# FMC_AWG_DAC_PSU_LDO.net
KiCad netlist of a schematic drawn in Altium Designer
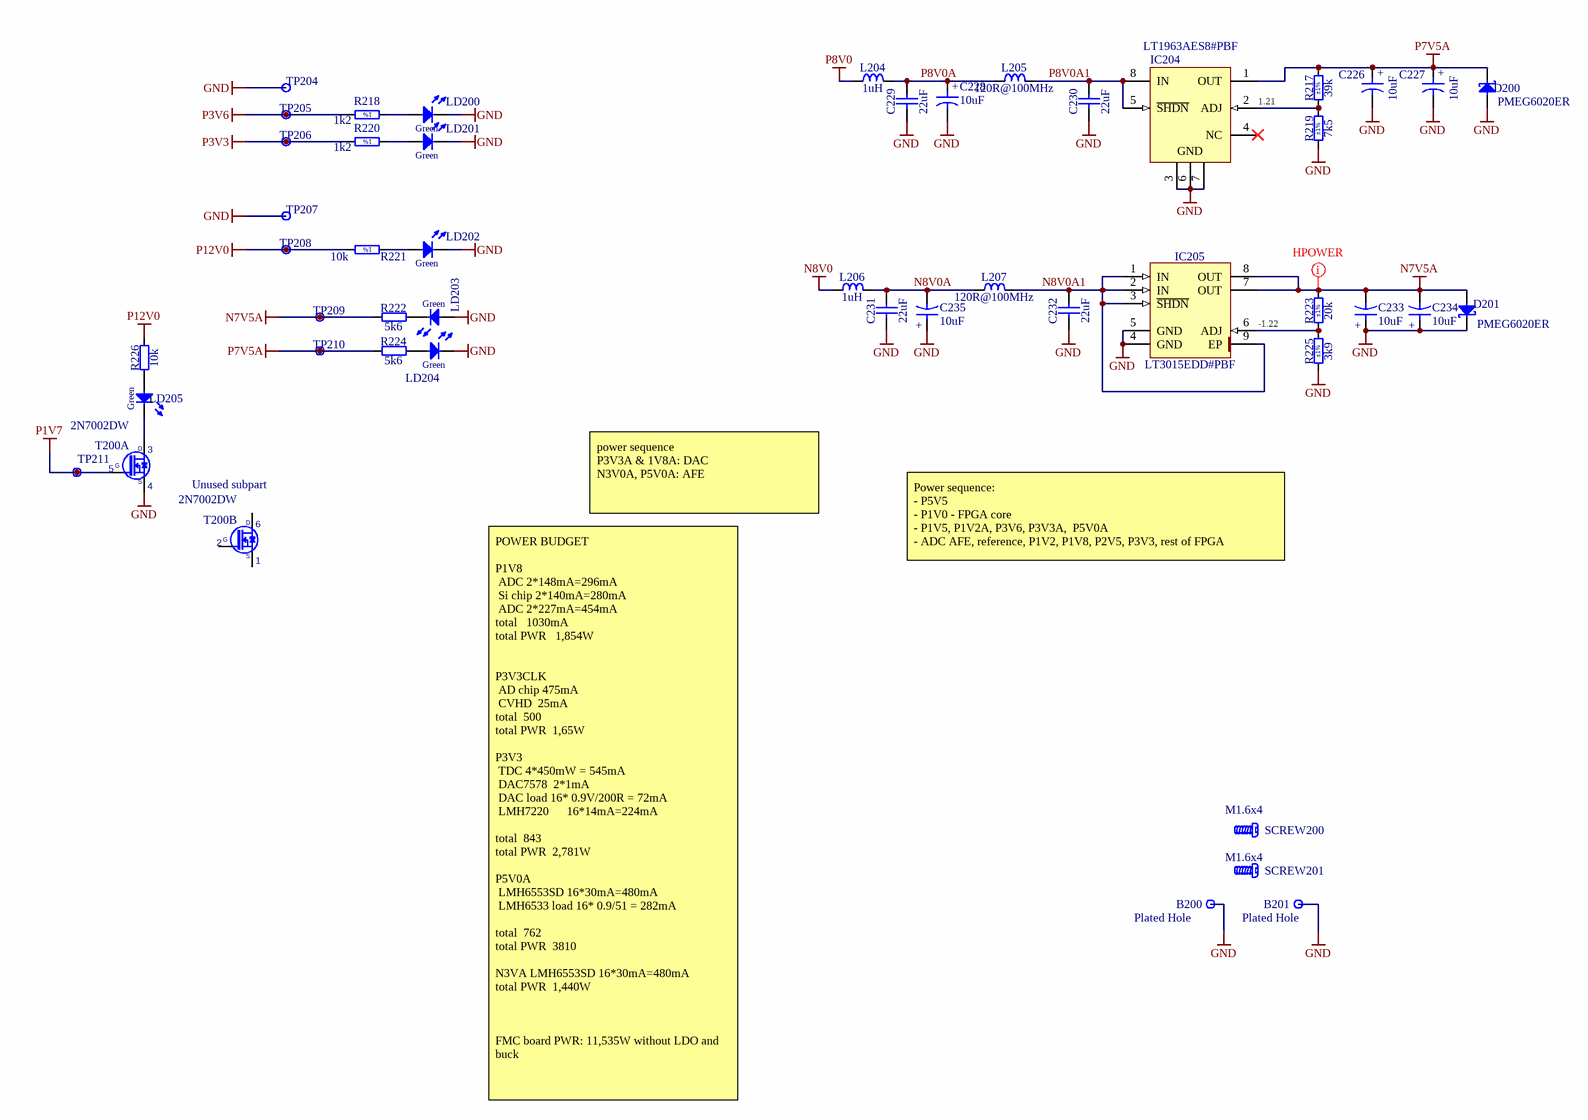
[diagram p0: FMC_AWG_DAC_PSU_LDO.SchDoc]

(export (version "E")
  (design (tool "Eeschema 10.0.6"))
  (components
    (comp (ref "B200")
      (value "Plated Hole")
      (footprint "c300h160")
      (description "Single Terminal Socket")
      (fields (field (name "PART NUMBER") "PLATED_HOLE1.6_PAD3.0") (field (name "AUTHOR") "CERN DEM JMW"))
      (libsource (lib "Eletro-mechanical") (part "Single Terminal Socket"))
    )
    (comp (ref "B201")
      (value "Plated Hole")
      (footprint "c300h160")
      (description "Single Terminal Socket")
      (fields (field (name "PART NUMBER") "PLATED_HOLE1.6_PAD3.0") (field (name "AUTHOR") "CERN DEM JMW"))
      (libsource (lib "Eletro-mechanical") (part "Single Terminal Socket"))
    )
    (comp (ref "C226")
      (value "10uF")
      (footprint "CAPMP3216X180N")
      (description "Polarised capacitor")
      (fields
        (field (name "PART NUMBER") "CTE3216-18_10UF_16V_20%_AVX_TCJ")
        (field (name "VOLTAGE") "16V")
        (field (name "AUTHOR") "CERN DEM JLC")
      )
      (libsource (lib "Capacitors") (part "Capacitor - polarized"))
    )
    (comp (ref "C227")
      (value "10uF")
      (footprint "CAPMP3216X180N")
      (description "Polarised capacitor")
      (fields
        (field (name "PART NUMBER") "CTE3216-18_10UF_16V_20%_AVX_TCJ")
        (field (name "VOLTAGE") "16V")
        (field (name "AUTHOR") "CERN DEM JLC")
      )
      (libsource (lib "Capacitors") (part "Capacitor - polarized"))
    )
    (comp (ref "C228")
      (value "10uF")
      (footprint "CAPMP3216X180N")
      (description "Polarised capacitor")
      (fields
        (field (name "PART NUMBER") "CTE3216-18_10UF_16V_20%_AVX_TCJ")
        (field (name "VOLTAGE") "16V")
        (field (name "AUTHOR") "CERN DEM JLC")
      )
      (libsource (lib "Capacitors") (part "Capacitor - polarized"))
    )
    (comp (ref "C229")
      (value "22uF")
      (footprint "CAPC2012X135N")
      (description "Non-polarised capacitor")
      (fields
        (field (name "PART NUMBER") "CC0805_22UF_16V_10%_X5R")
        (field (name "VOLTAGE") "16V")
        (field (name "AUTHOR") "CERN DEM JLC")
      )
      (libsource (lib "Capacitors") (part "Capacitor - non polarized"))
    )
    (comp (ref "C230")
      (value "22uF")
      (footprint "CAPC2012X135N")
      (description "Non-polarised capacitor")
      (fields
        (field (name "PART NUMBER") "CC0805_22UF_16V_10%_X5R")
        (field (name "VOLTAGE") "16V")
        (field (name "AUTHOR") "CERN DEM JLC")
      )
      (libsource (lib "Capacitors") (part "Capacitor - non polarized"))
    )
    (comp (ref "C231")
      (value "22uF")
      (footprint "CAPC2012X135N")
      (description "Non-polarised capacitor")
      (fields
        (field (name "PART NUMBER") "CC0805_22UF_16V_10%_X5R")
        (field (name "VOLTAGE") "16V")
        (field (name "AUTHOR") "CERN DEM JLC")
      )
      (libsource (lib "Capacitors") (part "Capacitor - non polarized"))
    )
    (comp (ref "C232")
      (value "22uF")
      (footprint "CAPC2012X135N")
      (description "Non-polarised capacitor")
      (fields
        (field (name "PART NUMBER") "CC0805_22UF_16V_10%_X5R")
        (field (name "VOLTAGE") "16V")
        (field (name "AUTHOR") "CERN DEM JLC")
      )
      (libsource (lib "Capacitors") (part "Capacitor - non polarized"))
    )
    (comp (ref "C233")
      (value "10uF")
      (footprint "CAPMP3216X180N")
      (description "Polarised capacitor")
      (fields
        (field (name "PART NUMBER") "CTE3216-18_10UF_16V_20%_AVX_TCJ")
        (field (name "VOLTAGE") "16V")
        (field (name "AUTHOR") "CERN DEM JLC")
      )
      (libsource (lib "Capacitors") (part "Capacitor - polarized"))
    )
    (comp (ref "C234")
      (value "10uF")
      (footprint "CAPMP3216X180N")
      (description "Polarised capacitor")
      (fields
        (field (name "PART NUMBER") "CTE3216-18_10UF_16V_20%_AVX_TCJ")
        (field (name "VOLTAGE") "16V")
        (field (name "AUTHOR") "CERN DEM JLC")
      )
      (libsource (lib "Capacitors") (part "Capacitor - polarized"))
    )
    (comp (ref "C235")
      (value "10uF")
      (footprint "CAPMP3216X180N")
      (description "Polarised capacitor")
      (fields
        (field (name "PART NUMBER") "CTE3216-18_10UF_16V_20%_AVX_TCJ")
        (field (name "VOLTAGE") "16V")
        (field (name "AUTHOR") "CERN DEM JLC")
      )
      (libsource (lib "Capacitors") (part "Capacitor - polarized"))
    )
    (comp (ref "D200")
      (value "PMEG6020ER")
      (footprint "SODFL3517X110N")
      (description "Schottky Diode")
      (fields
        (field (name "VOLTAGE") "60V")
        (field (name "POWER") "2A")
        (field (name "AUTHOR") "CERN DEM JMW")
      )
      (libsource (lib "ICs And Semiconductors") (part "Diode Schottky"))
    )
    (comp (ref "D201")
      (value "PMEG6020ER")
      (footprint "SODFL3517X110N")
      (description "Schottky Diode")
      (fields
        (field (name "VOLTAGE") "60V")
        (field (name "POWER") "2A")
        (field (name "AUTHOR") "CERN DEM JMW")
      )
      (libsource (lib "ICs And Semiconductors") (part "Diode Schottky"))
    )
    (comp (ref "IC204")
      (value "LT1963AES8#PBF")
      (footprint "LT-S8-8_L")
      (fields (field (name "MANUFACTURER") "Linear Technology"))
      (libsource (lib "Altium Content Vault") (part "LT-LT1521_1963A-S8-8_B"))
    )
    (comp (ref "IC205")
      (value "LT3015EDD#PBF")
      (footprint "SON50P300X300X80-9N-R175X248")
      (description "1.5A, Low Noise, Negative Linear Regulator with Precision Current Limit")
      (fields (field (name "MANUFACTURER") "LINEAR TECHNOLOGY") (field (name "AUTHOR") "CERN DEM MR"))
      (libsource (lib "ICs And Semiconductors") (part "LT3015EDD"))
    )
    (comp (ref "L204")
      (value "1uH")
      (footprint "INDC2620X100N")
      (description "Inductor")
      (fields
        (field (name "PART NUMBER") "IND1008_1UH_20%_WURTH_74479787210B")
        (field (name "POWER") "1.95A")
        (field (name "AUTHOR") "CERN DEM JLC")
      )
      (libsource (lib "Inductors & Transformers") (part "Inductor"))
    )
    (comp (ref "L205")
      (value "120R@100MHz")
      (footprint "INDC1608X65N")
      (description "Inductor")
      (fields
        (field (name "PART NUMBER") "IND0603_MURATA_BLM18SG121TN1D")
        (field (name "POWER") "3A")
        (field (name "AUTHOR") "CERN DEM JLC")
      )
      (libsource (lib "Inductors & Transformers") (part "Inductor"))
    )
    (comp (ref "L206")
      (value "1uH")
      (footprint "INDC2620X100N")
      (description "Inductor")
      (fields
        (field (name "PART NUMBER") "IND1008_1UH_20%_WURTH_74479787210B")
        (field (name "POWER") "1.95A")
        (field (name "AUTHOR") "CERN DEM JLC")
      )
      (libsource (lib "Inductors & Transformers") (part "Inductor"))
    )
    (comp (ref "L207")
      (value "120R@100MHz")
      (footprint "INDC1608X65N")
      (description "Inductor")
      (fields
        (field (name "PART NUMBER") "IND0603_MURATA_BLM18SG121TN1D")
        (field (name "POWER") "3A")
        (field (name "AUTHOR") "CERN DEM JLC")
      )
      (libsource (lib "Inductors & Transformers") (part "Inductor"))
    )
    (comp (ref "LD200")
      (value "Green")
      (footprint "LED_KINGBRIGHT_KPH-1608CGCKr")
      (description "Green 0603")
      (fields
        (field (name "PART NUMBER") "LED_KINGBRIGHT_KPH-1608CGCK")
        (field (name "MANUFACTURER") "KINGBRIGHT")
        (field (name "AUTHOR") "CERN DEM JLC")
      )
      (libsource (lib "LIBRARY_SCH") (part "LED_0603_Green"))
    )
    (comp (ref "LD201")
      (value "Green")
      (footprint "LED_KINGBRIGHT_KPH-1608CGCKr")
      (description "Green 0603")
      (fields
        (field (name "PART NUMBER") "LED_KINGBRIGHT_KPH-1608CGCK")
        (field (name "MANUFACTURER") "KINGBRIGHT")
        (field (name "AUTHOR") "CERN DEM JLC")
      )
      (libsource (lib "LIBRARY_SCH") (part "LED_0603_Green"))
    )
    (comp (ref "LD202")
      (value "Green")
      (footprint "LED_KINGBRIGHT_KPH-1608CGCKr")
      (description "Green 0603")
      (fields
        (field (name "PART NUMBER") "LED_KINGBRIGHT_KPH-1608CGCK")
        (field (name "MANUFACTURER") "KINGBRIGHT")
        (field (name "AUTHOR") "CERN DEM JLC")
      )
      (libsource (lib "LIBRARY_SCH") (part "LED_0603_Green"))
    )
    (comp (ref "LD203")
      (value "Green")
      (footprint "LED_KINGBRIGHT_KPH-1608CGCK")
      (description "LED Green 1C 2A")
      (fields
        (field (name "PART NUMBER") "LED_KINGBRIGHT_KPH-1608CGCK")
        (field (name "MANUFACTURER") "KINGBRIGHT")
        (field (name "AUTHOR") "CERN DEM JLC")
      )
      (libsource (lib "ICs And Semiconductors") (part "LED Green 1C 2A"))
    )
    (comp (ref "LD204")
      (value "Green")
      (footprint "LED_KINGBRIGHT_KPH-1608CGCK")
      (description "LED Green 1C 2A")
      (fields
        (field (name "PART NUMBER") "LED_KINGBRIGHT_KPH-1608CGCK")
        (field (name "MANUFACTURER") "KINGBRIGHT")
        (field (name "AUTHOR") "CERN DEM JLC")
      )
      (libsource (lib "ICs And Semiconductors") (part "LED Green 1C 2A"))
    )
    (comp (ref "LD205")
      (value "Green")
      (footprint "LED_KINGBRIGHT_KPH-1608CGCK")
      (description "LED Green 1C 2A")
      (fields
        (field (name "PART NUMBER") "LED_KINGBRIGHT_KPH-1608CGCK")
        (field (name "MANUFACTURER") "KINGBRIGHT")
        (field (name "AUTHOR") "CERN DEM JLC")
      )
      (libsource (lib "ICs And Semiconductors") (part "LED Green 1C 2A"))
    )
    (comp (ref "R217")
      (value "39k")
      (footprint "RESC1005X40N")
      (description "Resistor - 1%")
      (fields
        (field (name "TOLERANCE") "±1%")
        (field (name "PART NUMBER") "R0402_39K_1%_0.0625W_100PPM")
        (field (name "POWER") "0.0625W")
        (field (name "AUTHOR") "CERN DEM JLC")
      )
      (libsource (lib "Resistors") (part "Resistor - 1%"))
    )
    (comp (ref "R218")
      (value "1k2")
      (footprint "RESC1608X55N")
      (description "Resistor - 1%")
      (fields
        (field (name "PART NUMBER") "R0603_1K2_1%_0.1W_100PPM")
        (field (name "POWER") "0.1W")
        (field (name "AUTHOR") "CERN DEM JLC")
      )
      (libsource (lib "") (part "Resistor - 1%_1"))
    )
    (comp (ref "R219")
      (value "7k5")
      (footprint "RESC1005X40N")
      (description "Resistor - 1%")
      (fields
        (field (name "TOLERANCE") "±1%")
        (field (name "PART NUMBER") "R0402_7K5_1%_0.0625W_100PPM")
        (field (name "POWER") "0.0625W")
        (field (name "AUTHOR") "CERN DEM JLC")
      )
      (libsource (lib "Resistors") (part "Resistor - 1%"))
    )
    (comp (ref "R220")
      (value "1k2")
      (footprint "RESC1608X55N")
      (description "Resistor - 1%")
      (fields
        (field (name "PART NUMBER") "R0603_1K2_1%_0.1W_100PPM")
        (field (name "POWER") "0.1W")
        (field (name "AUTHOR") "CERN DEM JLC")
      )
      (libsource (lib "") (part "Resistor - 1%_1"))
    )
    (comp (ref "R221")
      (value "10k")
      (footprint "RESC1005X40N")
      (description "Resistor - 1%")
      (fields
        (field (name "PART NUMBER") "R0402_10K_1%_0.0625W_100PPM")
        (field (name "POWER") "0.0625W")
        (field (name "AUTHOR") "CERN DEM JLC")
      )
      (libsource (lib "Resistors") (part "Resistor - 1%"))
    )
    (comp (ref "R222")
      (value "5k6")
      (footprint "RESC1005X40N")
      (description "Resistor - 1%")
      (fields
        (field (name "PART NUMBER") "R0402_5K6_1%_0.0625W_100PPM")
        (field (name "POWER") "0.0625W")
        (field (name "AUTHOR") "CERN DEM JLC")
      )
      (libsource (lib "Resistors") (part "Resistor - 1%"))
    )
    (comp (ref "R223")
      (value "20k")
      (footprint "RESC1005X40N")
      (description "Resistor - 1%")
      (fields
        (field (name "TOLERANCE") "±1%")
        (field (name "PART NUMBER") "R0402_20K_1%_0.0625W_100PPM")
        (field (name "POWER") "0.0625W")
        (field (name "AUTHOR") "CERN DEM JLC")
      )
      (libsource (lib "Resistors") (part "Resistor - 1%"))
    )
    (comp (ref "R224")
      (value "5k6")
      (footprint "RESC1005X40N")
      (description "Resistor - 1%")
      (fields
        (field (name "PART NUMBER") "R0402_5K6_1%_0.0625W_100PPM")
        (field (name "POWER") "0.0625W")
        (field (name "AUTHOR") "CERN DEM JLC")
      )
      (libsource (lib "Resistors") (part "Resistor - 1%"))
    )
    (comp (ref "R225")
      (value "3k9")
      (footprint "RESC1005X40N")
      (description "Resistor - 1%")
      (fields
        (field (name "TOLERANCE") "±1%")
        (field (name "PART NUMBER") "R0402_3K9_1%_0.0625W_100PPM")
        (field (name "POWER") "0.0625W")
        (field (name "AUTHOR") "CERN DEM JLC")
      )
      (libsource (lib "Resistors") (part "Resistor - 1%"))
    )
    (comp (ref "R226")
      (value "10k")
      (footprint "RESC1005X40N")
      (description "Resistor - 1%")
      (fields
        (field (name "PART NUMBER") "R0402_10K_1%_0.0625W_100PPM")
        (field (name "POWER") "0.0625W")
        (field (name "AUTHOR") "CERN DEM JLC")
      )
      (libsource (lib "Resistors") (part "Resistor - 1%"))
    )
    (comp (ref "SCREW200")
      (value "M1.6x4")
      (footprint "BOSSARD_B1.6X4/BN660_v")
      (description "Screw")
      (fields
        (field (name "PART NUMBER") "BOSSARD_B1.6X4/BN660")
        (field (name "MANUFACTURER") "BOSSARD")
        (field (name "AUTHOR") "GK")
      )
      (libsource (lib "Mechanical") (part "MECH_SCREW_M1.6x4"))
    )
    (comp (ref "SCREW201")
      (value "M1.6x4")
      (footprint "BOSSARD_B1.6X4/BN660_v")
      (description "Screw")
      (fields
        (field (name "PART NUMBER") "BOSSARD_B1.6X4/BN660")
        (field (name "MANUFACTURER") "BOSSARD")
        (field (name "AUTHOR") "GK")
      )
      (libsource (lib "Mechanical") (part "MECH_SCREW_M1.6x4"))
    )
    (comp (ref "T200")
      (value "2N7002DW")
      (footprint "SOT65P210X110-6N")
      (description "60 V, 115 mA, Dual N-Channel Field Effect Transistor, Enhancement Mode")
      (fields (field (name "MANUFACTURER") "ON SEMICONDUCTOR") (field (name "AUTHOR") "CERN DEM BC"))
      (libsource (lib "ICs And Semiconductors") (part "2N7002DW"))
    )
    (comp (ref "TP204")
      (value "Test Point")
      (footprint "TPS127")
      (fields (field (name "PART NUMBER") "SMD_PAD_1.27X1.27MM") (field (name "AUTHOR") "CERN DEM JLC"))
      (libsource (lib "Eletro-mechanical") (part "Test Point"))
    )
    (comp (ref "TP205")
      (value "Test Point")
      (footprint "TPS127")
      (fields (field (name "PART NUMBER") "SMD_PAD_1.27X1.27MM") (field (name "AUTHOR") "CERN DEM JLC"))
      (libsource (lib "Eletro-mechanical") (part "Test Point"))
    )
    (comp (ref "TP206")
      (value "Test Point")
      (footprint "TPS127")
      (fields (field (name "PART NUMBER") "SMD_PAD_1.27X1.27MM") (field (name "AUTHOR") "CERN DEM JLC"))
      (libsource (lib "Eletro-mechanical") (part "Test Point"))
    )
    (comp (ref "TP207")
      (value "Test Point")
      (footprint "TPS127")
      (fields (field (name "PART NUMBER") "SMD_PAD_1.27X1.27MM") (field (name "AUTHOR") "CERN DEM JLC"))
      (libsource (lib "Eletro-mechanical") (part "Test Point"))
    )
    (comp (ref "TP208")
      (value "Test Point")
      (footprint "TPS127")
      (fields (field (name "PART NUMBER") "SMD_PAD_1.27X1.27MM") (field (name "AUTHOR") "CERN DEM JLC"))
      (libsource (lib "Eletro-mechanical") (part "Test Point"))
    )
    (comp (ref "TP209")
      (value "Test Point")
      (footprint "TPS127")
      (fields (field (name "PART NUMBER") "SMD_PAD_1.27X1.27MM") (field (name "AUTHOR") "CERN DEM JLC"))
      (libsource (lib "Eletro-mechanical") (part "Test Point"))
    )
    (comp (ref "TP210")
      (value "Test Point")
      (footprint "TPS127")
      (fields (field (name "PART NUMBER") "SMD_PAD_1.27X1.27MM") (field (name "AUTHOR") "CERN DEM JLC"))
      (libsource (lib "Eletro-mechanical") (part "Test Point"))
    )
    (comp (ref "TP211")
      (value "Test Point")
      (footprint "TPS127")
      (fields (field (name "PART NUMBER") "SMD_PAD_1.27X1.27MM") (field (name "AUTHOR") "CERN DEM JLC"))
      (libsource (lib "Eletro-mechanical") (part "Test Point"))
    )
  )
  (nets
    (net (code "1") (name "/N8V0A") (class "Default")
      (node (ref "C231") (pin "2") (pinfunction "2_2") (pintype "passive"))
      (node (ref "C235") (pin "2") (pinfunction "2_2") (pintype "passive"))
      (node (ref "L206") (pin "2") (pinfunction "2_2") (pintype "passive"))
      (node (ref "L207") (pin "1") (pinfunction "1_1") (pintype "passive"))
    )
    (net (code "2") (name "/N8V0A1") (class "Default")
      (node (ref "C232") (pin "2") (pinfunction "2_2") (pintype "passive"))
      (node (ref "IC205") (pin "1") (pinfunction "IN_1") (pintype "input"))
      (node (ref "IC205") (pin "2") (pinfunction "IN_2") (pintype "input"))
      (node (ref "IC205") (pin "3") (pinfunction "~{SHDN}_3") (pintype "input"))
      (node (ref "IC205") (pin "9") (pinfunction "EP_9") (pintype "power_in"))
      (node (ref "L207") (pin "2") (pinfunction "2_2") (pintype "passive"))
    )
    (net (code "3") (name "/P8V0A") (class "Default")
      (node (ref "C228") (pin "1") (pinfunction "1_1") (pintype "passive"))
      (node (ref "C229") (pin "2") (pinfunction "2_2") (pintype "passive"))
      (node (ref "L204") (pin "2") (pinfunction "2_2") (pintype "passive"))
      (node (ref "L205") (pin "1") (pinfunction "1_1") (pintype "passive"))
    )
    (net (code "4") (name "/P8V0A1") (class "Default")
      (node (ref "C230") (pin "2") (pinfunction "2_2") (pintype "passive"))
      (node (ref "IC204") (pin "5") (pinfunction "~{SHDN}_5") (pintype "input"))
      (node (ref "IC204") (pin "8") (pinfunction "IN_8") (pintype "power_in"))
      (node (ref "L205") (pin "2") (pinfunction "2_2") (pintype "passive"))
    )
    (net (code "5") (name "GND") (class "Default")
      (node (ref "B200") (pin "1") (pinfunction "1_1") (pintype "bidirectional"))
      (node (ref "B201") (pin "1") (pinfunction "1_1") (pintype "bidirectional"))
      (node (ref "C226") (pin "2") (pinfunction "2_2") (pintype "passive"))
      (node (ref "C227") (pin "2") (pinfunction "2_2") (pintype "passive"))
      (node (ref "C228") (pin "2") (pinfunction "2_2") (pintype "passive"))
      (node (ref "C229") (pin "1") (pinfunction "1_1") (pintype "passive"))
      (node (ref "C230") (pin "1") (pinfunction "1_1") (pintype "passive"))
      (node (ref "C231") (pin "1") (pinfunction "1_1") (pintype "passive"))
      (node (ref "C232") (pin "1") (pinfunction "1_1") (pintype "passive"))
      (node (ref "C233") (pin "1") (pinfunction "1_1") (pintype "passive"))
      (node (ref "C234") (pin "1") (pinfunction "1_1") (pintype "passive"))
      (node (ref "C235") (pin "1") (pinfunction "1_1") (pintype "passive"))
      (node (ref "D200") (pin "2") (pinfunction "A_2") (pintype "passive"))
      (node (ref "D201") (pin "1") (pinfunction "C_1") (pintype "passive"))
      (node (ref "IC204") (pin "3") (pinfunction "GND_3") (pintype "power_in"))
      (node (ref "IC204") (pin "6") (pinfunction "GND_6") (pintype "power_in"))
      (node (ref "IC204") (pin "7") (pinfunction "GND_7") (pintype "power_in"))
      (node (ref "IC205") (pin "4") (pinfunction "GND_4") (pintype "power_in"))
      (node (ref "IC205") (pin "5") (pinfunction "GND_5") (pintype "power_in"))
      (node (ref "LD200") (pin "1") (pinfunction "C_1") (pintype "passive"))
      (node (ref "LD201") (pin "1") (pinfunction "C_1") (pintype "passive"))
      (node (ref "LD202") (pin "1") (pinfunction "C_1") (pintype "passive"))
      (node (ref "LD203") (pin "2") (pinfunction "A_2") (pintype "passive"))
      (node (ref "LD204") (pin "1") (pinfunction "C_1") (pintype "passive"))
      (node (ref "R219") (pin "1") (pinfunction "1_1") (pintype "passive"))
      (node (ref "R225") (pin "1") (pinfunction "1_1") (pintype "passive"))
      (node (ref "T200") (pin "4") (pinfunction "S1_4") (pintype "passive"))
      (node (ref "TP204") (pin "1") (pinfunction "1_1") (pintype "bidirectional"))
      (node (ref "TP207") (pin "1") (pinfunction "1_1") (pintype "bidirectional"))
    )
    (net (code "6") (name "N7V5A") (class "Default")
      (node (ref "C233") (pin "2") (pinfunction "2_2") (pintype "passive"))
      (node (ref "C234") (pin "2") (pinfunction "2_2") (pintype "passive"))
      (node (ref "D201") (pin "2") (pinfunction "A_2") (pintype "passive"))
      (node (ref "IC205") (pin "7") (pinfunction "OUT_7") (pintype "power_in"))
      (node (ref "IC205") (pin "8") (pinfunction "OUT_8") (pintype "power_in"))
      (node (ref "R222") (pin "1") (pinfunction "1_1") (pintype "passive"))
      (node (ref "R223") (pin "2") (pinfunction "2_2") (pintype "passive"))
      (node (ref "TP209") (pin "1") (pinfunction "1_1") (pintype "bidirectional"))
    )
    (net (code "7") (name "N8V0") (class "Default")
      (node (ref "L206") (pin "1") (pinfunction "1_1") (pintype "passive"))
    )
    (net (code "8") (name "Net-(IC204-ADJ)") (class "Default")
      (node (ref "IC204") (pin "2") (pinfunction "ADJ_2") (pintype "input"))
      (node (ref "R217") (pin "1") (pinfunction "1_1") (pintype "passive"))
      (node (ref "R219") (pin "2") (pinfunction "2_2") (pintype "passive"))
    )
    (net (code "9") (name "Net-(IC205-ADJ)") (class "Default")
      (node (ref "IC205") (pin "6") (pinfunction "ADJ_6") (pintype "input"))
      (node (ref "R223") (pin "1") (pinfunction "1_1") (pintype "passive"))
      (node (ref "R225") (pin "2") (pinfunction "2_2") (pintype "passive"))
    )
    (net (code "10") (name "Net-(LD200-A)") (class "Default")
      (node (ref "LD200") (pin "2") (pinfunction "A_2") (pintype "passive"))
      (node (ref "R218") (pin "1") (pinfunction "1_1") (pintype "passive"))
    )
    (net (code "11") (name "Net-(LD201-A)") (class "Default")
      (node (ref "LD201") (pin "2") (pinfunction "A_2") (pintype "passive"))
      (node (ref "R220") (pin "1") (pinfunction "1_1") (pintype "passive"))
    )
    (net (code "12") (name "Net-(LD202-A)") (class "Default")
      (node (ref "LD202") (pin "2") (pinfunction "A_2") (pintype "passive"))
      (node (ref "R221") (pin "1") (pinfunction "1_1") (pintype "passive"))
    )
    (net (code "13") (name "Net-(LD203-C)") (class "Default")
      (node (ref "LD203") (pin "1") (pinfunction "C_1") (pintype "passive"))
      (node (ref "R222") (pin "2") (pinfunction "2_2") (pintype "passive"))
    )
    (net (code "14") (name "Net-(LD204-A)") (class "Default")
      (node (ref "LD204") (pin "2") (pinfunction "A_2") (pintype "passive"))
      (node (ref "R224") (pin "2") (pinfunction "2_2") (pintype "passive"))
    )
    (net (code "15") (name "Net-(LD205-A)") (class "Default")
      (node (ref "LD205") (pin "2") (pinfunction "A_2") (pintype "passive"))
      (node (ref "R226") (pin "1") (pinfunction "1_1") (pintype "passive"))
    )
    (net (code "16") (name "Net-(LD205-C)") (class "Default")
      (node (ref "LD205") (pin "1") (pinfunction "C_1") (pintype "passive"))
      (node (ref "T200") (pin "3") (pinfunction "D1_3") (pintype "passive"))
    )
    (net (code "17") (name "P1V7") (class "Default")
      (node (ref "T200") (pin "5") (pinfunction "G1_5") (pintype "passive"))
      (node (ref "TP211") (pin "1") (pinfunction "1_1") (pintype "bidirectional"))
    )
    (net (code "18") (name "P3V3") (class "Default")
      (node (ref "R220") (pin "2") (pinfunction "2_2") (pintype "passive"))
      (node (ref "TP206") (pin "1") (pinfunction "1_1") (pintype "bidirectional"))
    )
    (net (code "19") (name "P3V6") (class "Default")
      (node (ref "R218") (pin "2") (pinfunction "2_2") (pintype "passive"))
      (node (ref "TP205") (pin "1") (pinfunction "1_1") (pintype "bidirectional"))
    )
    (net (code "20") (name "P7V5A") (class "Default")
      (node (ref "C226") (pin "1") (pinfunction "1_1") (pintype "passive"))
      (node (ref "C227") (pin "1") (pinfunction "1_1") (pintype "passive"))
      (node (ref "D200") (pin "1") (pinfunction "C_1") (pintype "passive"))
      (node (ref "IC204") (pin "1") (pinfunction "OUT_1") (pintype "power_in"))
      (node (ref "R217") (pin "2") (pinfunction "2_2") (pintype "passive"))
      (node (ref "R224") (pin "1") (pinfunction "1_1") (pintype "passive"))
      (node (ref "TP210") (pin "1") (pinfunction "1_1") (pintype "bidirectional"))
    )
    (net (code "21") (name "P8V0") (class "Default")
      (node (ref "L204") (pin "1") (pinfunction "1_1") (pintype "passive"))
    )
    (net (code "22") (name "P12V0") (class "Default")
      (node (ref "R221") (pin "2") (pinfunction "2_2") (pintype "passive"))
      (node (ref "R226") (pin "2") (pinfunction "2_2") (pintype "passive"))
      (node (ref "TP208") (pin "1") (pinfunction "1_1") (pintype "bidirectional"))
    )
    (net (code "23") (name "unconnected-(IC204-NC-Pad4)") (class "Default")
      (node (ref "IC204") (pin "4") (pinfunction "NC_4") (pintype "passive+no_connect"))
    )
    (net (code "24") (name "unconnected-(T200B-D2-Pad6)") (class "Default")
      (node (ref "T200") (pin "6") (pinfunction "D2_6") (pintype "passive"))
    )
    (net (code "25") (name "unconnected-(T200B-G2-Pad2)") (class "Default")
      (node (ref "T200") (pin "2") (pinfunction "G2_2") (pintype "passive"))
    )
    (net (code "26") (name "unconnected-(T200B-S2-Pad1)") (class "Default")
      (node (ref "T200") (pin "1") (pinfunction "S2_1") (pintype "passive"))
    )
  )
)
